# SeccionHimfu.net
KiCad netlist of a schematic drawn in Altium Designer
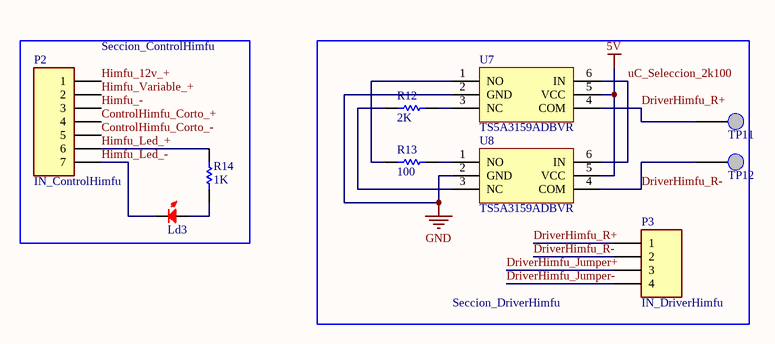
[diagram p0: SeccionHimfu.SchDoc]

(export (version "E")
  (design (tool "Eeschema 10.0.6"))
  (components
    (comp (ref "Ld3")
      (value "PinesParaLed")
      (footprint "Nahuel_TH_BODY:Jumper-Simple")
      (description "CONN HEADER 2 POS 2.54")
      (fields (field (name "PUBLISHER") "Altium Limited"))
      (libsource (lib "Nahuel_TH_BODY") (part "PinesParaLed"))
    )
    (comp (ref "P2")
      (value "IN_ControlHimfu")
      (footprint "Nahuel_Connectors_BODY:B7B-XH-A_3D")
      (description "CONN HEADER XH TOP 7POS 2.5MM")
      (fields (field (name "PUBLISHER") "Altium Limited"))
      (libsource (lib "Nahuel_Connectors_BODY") (part "JST_2.5_7"))
    )
    (comp (ref "P3")
      (value "IN_DriverHimfu")
      (footprint "B4B-XH-A_3D")
      (description "CONN HEADER XH TOP 4POS 2.5MM")
      (fields (field (name "PUBLISHER") "Altium Limited"))
      (libsource (lib "Nahuel_Connectors_BODY") (part "JST_2.5_4"))
    )
    (comp (ref "R12")
      (value "2K")
      (footprint "Nahuel_SMD_Body:R_0805")
      (description "RES SMD 2K OHM 1% 1/8W 0805")
      (fields (field (name "PUBLISHER") "Altium Limited"))
      (libsource (lib "Nahuel_SMD_Body") (part "R_2k"))
    )
    (comp (ref "R13")
      (value "100")
      (footprint "Nahuel_SMD_Body:R_0805")
      (description "RES SMD 100 OHM 1% 1/8W 0805")
      (fields (field (name "PUBLISHER") "Altium Limited"))
      (libsource (lib "Nahuel_SMD_Body") (part "R_100"))
    )
    (comp (ref "R14")
      (value "1K")
      (footprint "Nahuel_SMD_Body:R_0805")
      (description "RES SMD 1K OHM 1% 1/8W 0805")
      (fields (field (name "PUBLISHER") "Altium Limited"))
      (libsource (lib "Nahuel_SMD_Body") (part "R_1k"))
    )
    (comp (ref "TP11")
      (value "DRH+")
      (footprint "Nahuel_TH_BODY:TP-5002")
      (fields (field (name "PUBLISHER") "Altium Limited"))
      (libsource (lib "Nahuel_TH_BODY") (part "TestPoint"))
    )
    (comp (ref "TP12")
      (value "DRH-")
      (footprint "Nahuel_TH_BODY:TP-5002")
      (fields (field (name "PUBLISHER") "Altium Limited"))
      (libsource (lib "Nahuel_TH_BODY") (part "TestPoint"))
    )
    (comp (ref "U7")
      (value "TS5A3159ADBVR")
      (footprint "Nahuel_SMD_Body:SOT23-6")
      (description "IC SWITCH SPDT SOT23-6")
      (fields (field (name "PUBLISHER") "Altium Limited"))
      (libsource (lib "Nahuel_SMD_Body") (part "TS5A3159ADBVR"))
    )
    (comp (ref "U8")
      (value "TS5A3159ADBVR")
      (footprint "Nahuel_SMD_Body:SOT23-6")
      (description "IC SWITCH SPDT SOT23-6")
      (fields (field (name "PUBLISHER") "Altium Limited"))
      (libsource (lib "Nahuel_SMD_Body") (part "TS5A3159ADBVR"))
    )
  )
  (nets
    (net (code "1") (name "/ControlHimfu_Corto_+") (class "Default")
      (node (ref "P2") (pin "4") (pinfunction "4_4") (pintype "passive"))
    )
    (net (code "2") (name "/ControlHimfu_Corto_-") (class "Default")
      (node (ref "P2") (pin "5") (pinfunction "5_5") (pintype "passive"))
    )
    (net (code "3") (name "/DriverHimfu_Jumper+") (class "Default")
      (node (ref "P3") (pin "3") (pinfunction "3_3") (pintype "passive"))
    )
    (net (code "4") (name "/DriverHimfu_Jumper-") (class "Default")
      (node (ref "P3") (pin "4") (pinfunction "4_4") (pintype "passive"))
    )
    (net (code "5") (name "/DriverHimfu_R+") (class "Default")
      (node (ref "P3") (pin "1") (pinfunction "1_1") (pintype "passive"))
      (node (ref "TP11") (pin "1") (pinfunction "1_1") (pintype "passive"))
      (node (ref "U7") (pin "4") (pinfunction "COM_4") (pintype "passive"))
    )
    (net (code "6") (name "/DriverHimfu_R-") (class "Default")
      (node (ref "P3") (pin "2") (pinfunction "2_2") (pintype "passive"))
      (node (ref "TP12") (pin "1") (pinfunction "1_1") (pintype "passive"))
      (node (ref "U8") (pin "4") (pinfunction "COM_4") (pintype "passive"))
    )
    (net (code "7") (name "/Himfu_-") (class "Default")
      (node (ref "P2") (pin "3") (pinfunction "3_3") (pintype "passive"))
    )
    (net (code "8") (name "/Himfu_12v_+") (class "Default")
      (node (ref "P2") (pin "1") (pinfunction "1_1") (pintype "passive"))
    )
    (net (code "9") (name "/Himfu_Led_+") (class "Default")
      (node (ref "P2") (pin "6") (pinfunction "6_6") (pintype "passive"))
      (node (ref "R14") (pin "2") (pinfunction "2_2") (pintype "passive"))
    )
    (net (code "10") (name "/Himfu_Led_-") (class "Default")
      (node (ref "Ld3") (pin "2") (pinfunction "2_2") (pintype "passive"))
      (node (ref "P2") (pin "7") (pinfunction "7_7") (pintype "passive"))
    )
    (net (code "11") (name "/Himfu_Variable_+") (class "Default")
      (node (ref "P2") (pin "2") (pinfunction "2_2") (pintype "passive"))
    )
    (net (code "12") (name "/uC_Seleccion_2k100") (class "Default")
      (node (ref "U7") (pin "6") (pinfunction "IN_6") (pintype "passive"))
      (node (ref "U8") (pin "6") (pinfunction "IN_6") (pintype "passive"))
    )
    (net (code "13") (name "5V") (class "Default")
      (node (ref "U7") (pin "5") (pinfunction "VCC_5") (pintype "passive"))
      (node (ref "U8") (pin "5") (pinfunction "VCC_5") (pintype "passive"))
    )
    (net (code "14") (name "GND") (class "Default")
      (node (ref "U7") (pin "2") (pinfunction "GND_2") (pintype "passive"))
      (node (ref "U8") (pin "2") (pinfunction "GND_2") (pintype "passive"))
    )
    (net (code "15") (name "Net-(Ld3-Pad1)") (class "Default")
      (node (ref "Ld3") (pin "1") (pinfunction "1_1") (pintype "passive"))
      (node (ref "R14") (pin "1") (pinfunction "1_1") (pintype "passive"))
    )
    (net (code "16") (name "Net-(U7-NC)") (class "Default")
      (node (ref "R12") (pin "2") (pinfunction "2_2") (pintype "passive"))
      (node (ref "U7") (pin "3") (pinfunction "NC_3") (pintype "passive"))
    )
    (net (code "17") (name "Net-(U7-NO)") (class "Default")
      (node (ref "R13") (pin "1") (pinfunction "1_1") (pintype "passive"))
      (node (ref "U7") (pin "1") (pinfunction "NO_1") (pintype "passive"))
    )
    (net (code "18") (name "Net-(U8-NC)") (class "Default")
      (node (ref "R12") (pin "1") (pinfunction "1_1") (pintype "passive"))
      (node (ref "U8") (pin "3") (pinfunction "NC_3") (pintype "passive"))
    )
    (net (code "19") (name "Net-(U8-NO)") (class "Default")
      (node (ref "R13") (pin "2") (pinfunction "2_2") (pintype "passive"))
      (node (ref "U8") (pin "1") (pinfunction "NO_1") (pintype "passive"))
    )
  )
)
